# TurbochargerController_IR.net
KiCad netlist of a schematic drawn in EAGLE
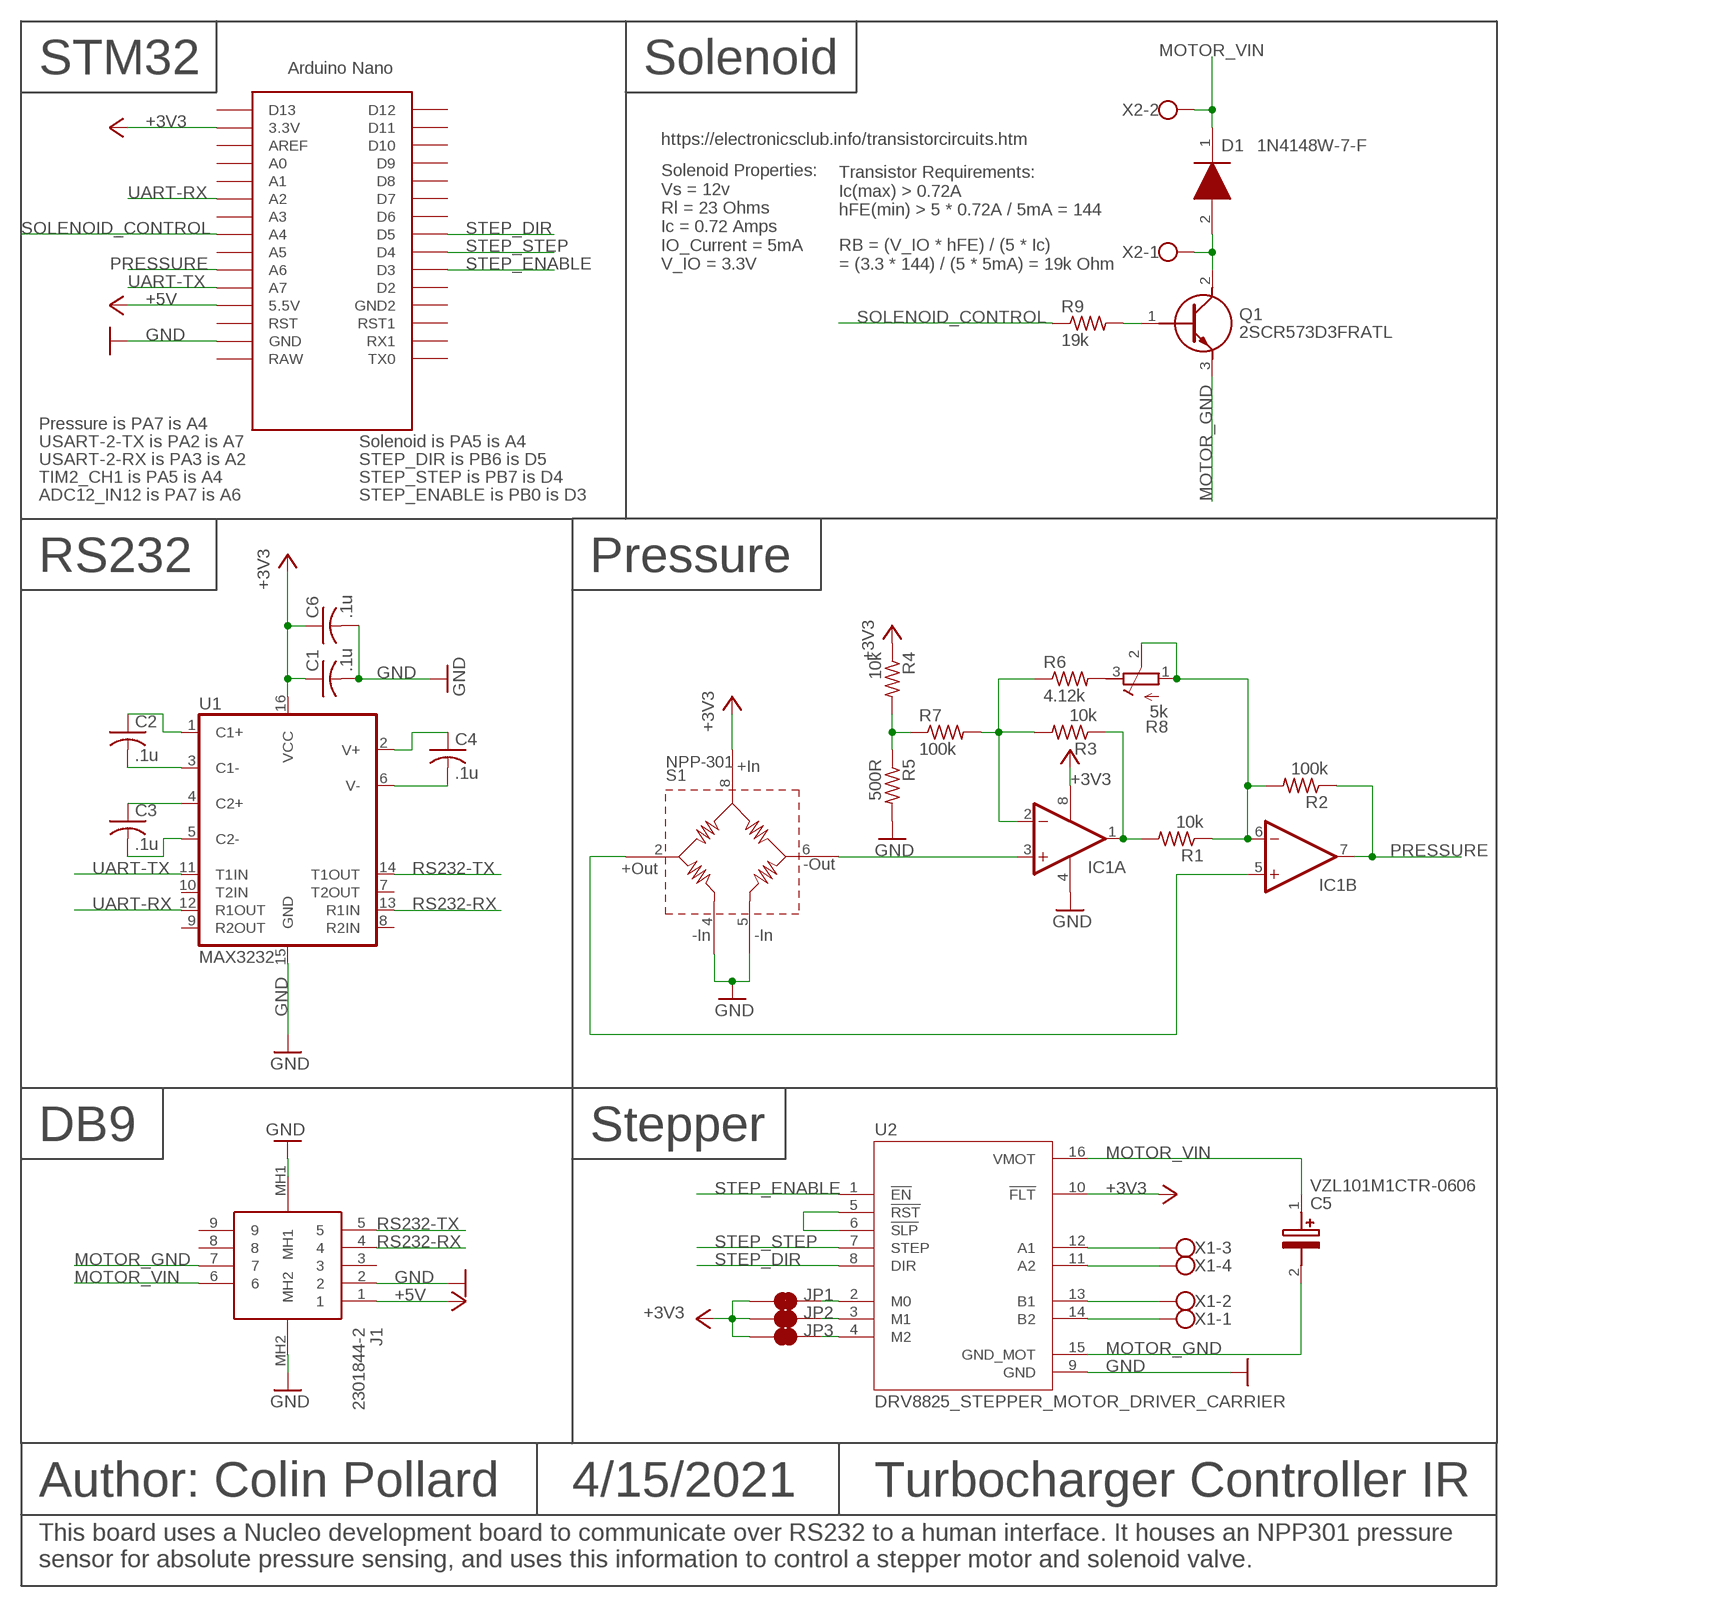
[diagram p0: schematic, sheet 1]

(export (version "E")
  (design (tool "Eeschema 10.0.6"))
  (components
    (comp (ref "C1")
      (value ".1u")
      (footprint "eagle-import:C1206")
      (libsource (lib "eagle-import") (part "C-USC1206"))
    )
    (comp (ref "C2")
      (value ".1u")
      (footprint "eagle-import:C1206")
      (libsource (lib "eagle-import") (part "C-USC1206"))
    )
    (comp (ref "C3")
      (value ".1u")
      (footprint "eagle-import:C1206")
      (libsource (lib "eagle-import") (part "C-USC1206"))
    )
    (comp (ref "C4")
      (value ".1u")
      (footprint "eagle-import:C1206")
      (libsource (lib "eagle-import") (part "C-USC1206"))
    )
    (comp (ref "C5")
      (value "VZL101M1CTR-0606")
      (footprint "eagle-import:CAPAE660X610N")
      (fields (field (name "MOUSER_PART_NUMBER") "140-VZL101M1CTR-0606"))
      (libsource (lib "eagle-import") (part "VZL101M1CTR-0606"))
    )
    (comp (ref "C6")
      (value ".1u")
      (footprint "eagle-import:C1206")
      (libsource (lib "eagle-import") (part "C-USC1206"))
    )
    (comp (ref "D1")
      (value "1N4148W-7-F")
      (footprint "eagle-import:SOD3716X145N")
      (fields (field (name "MOUSER_PART_NUMBER") "621-1N4148W-F"))
      (libsource (lib "eagle-import") (part "1N4148W-7-F"))
    )
    (comp (ref "IC1")
      (value "TL072D")
      (footprint "eagle-import:SO08")
      (libsource (lib "eagle-import") (part "TL072D"))
    )
    (comp (ref "J1")
      (value "2301844-2")
      (footprint "eagle-import:23018442")
      (fields (field (name "MOUSER_PART_NUMBER") "571-2301844-2"))
      (libsource (lib "eagle-import") (part "2301844-2"))
    )
    (comp (ref "JP1")
      (value "JUMPER-SMT_2_NC_TRACE_SILK")
      (footprint "eagle-import:SMT-JUMPER_2_NC_TRACE_SILK")
      (libsource (lib "eagle-import") (part "JUMPER-SMT_2_NC_TRACE_SILK"))
    )
    (comp (ref "JP2")
      (value "JUMPER-SMT_2_NC_TRACE_SILK")
      (footprint "eagle-import:SMT-JUMPER_2_NC_TRACE_SILK")
      (libsource (lib "eagle-import") (part "JUMPER-SMT_2_NC_TRACE_SILK"))
    )
    (comp (ref "JP3")
      (value "JUMPER-SMT_2_NC_TRACE_SILK")
      (footprint "eagle-import:SMT-JUMPER_2_NC_TRACE_SILK")
      (libsource (lib "eagle-import") (part "JUMPER-SMT_2_NC_TRACE_SILK"))
    )
    (comp (ref "Q1")
      (value "2SCR573D3FRATL")
      (footprint "eagle-import:2SCR573D3FRATL")
      (fields (field (name "MOUSER_PART_NUMBER") "755-2SCR573D3FRATL"))
      (libsource (lib "eagle-import") (part "2SCR573D3FRATL"))
    )
    (comp (ref "R1")
      (value "10k")
      (footprint "eagle-import:R1206")
      (libsource (lib "eagle-import") (part "R-US_R1206"))
    )
    (comp (ref "R2")
      (value "100k")
      (footprint "eagle-import:R1206")
      (libsource (lib "eagle-import") (part "R-US_R1206"))
    )
    (comp (ref "R3")
      (value "10k")
      (footprint "eagle-import:R1206")
      (libsource (lib "eagle-import") (part "R-US_R1206"))
    )
    (comp (ref "R4")
      (value "10k")
      (footprint "eagle-import:R1206")
      (libsource (lib "eagle-import") (part "R-US_R1206"))
    )
    (comp (ref "R5")
      (value "500R")
      (footprint "eagle-import:R1206")
      (libsource (lib "eagle-import") (part "R-US_R1206"))
    )
    (comp (ref "R6")
      (value "4.12k")
      (footprint "eagle-import:R1206")
      (libsource (lib "eagle-import") (part "R-US_R1206"))
    )
    (comp (ref "R7")
      (value "100k")
      (footprint "eagle-import:R1206")
      (libsource (lib "eagle-import") (part "R-US_R1206"))
    )
    (comp (ref "R8")
      (value "5k")
      (footprint "eagle-import:RTRIM3296W")
      (libsource (lib "eagle-import") (part "R-TRIMM3296W"))
    )
    (comp (ref "R9")
      (value "19k")
      (footprint "eagle-import:R1206")
      (libsource (lib "eagle-import") (part "R-US_R1206"))
    )
    (comp (ref "S1")
      (value "NPP-301")
      (footprint "eagle-import:SO08")
      (libsource (lib "eagle-import") (part "NPP-301"))
    )
    (comp (ref "U$1")
      (value "NANO")
      (footprint "eagle-import:NANO")
      (libsource (lib "eagle-import") (part "NANO"))
    )
    (comp (ref "U1")
      (value "MAX3232")
      (footprint "eagle-import:SO16")
      (libsource (lib "eagle-import") (part "MAX2323SOIC16"))
    )
    (comp (ref "U2")
      (value "DRV8825_STEPPER_MOTOR_DRIVER_CARRIER")
      (footprint "eagle-import:IC_DRV8825_STEPPER_MOTOR_DRIVER_CARRIER")
      (fields (field (name "MF") "Pololu") (field (name "MP") "DRV8825 STEPPER MOTOR DRIVER CARRIER"))
      (libsource (lib "eagle-import") (part "DRV8825_STEPPER_MOTOR_DRIVER_CARRIER"))
    )
    (comp (ref "X1")
      (value "W237-4")
      (footprint "eagle-import:W237-4")
      (libsource (lib "eagle-import") (part "W237-4"))
    )
    (comp (ref "X2")
      (value "W237-102")
      (footprint "eagle-import:W237-102")
      (fields (field (name "MPN") "237-102"))
      (libsource (lib "eagle-import") (part "W237-102"))
    )
  )
  (nets
    (net (code "1") (name "+3V3") (class "Default")
      (node (ref "C1") (pin "1") (pinfunction "1_1") (pintype "passive"))
      (node (ref "C6") (pin "1") (pinfunction "1_1") (pintype "passive"))
      (node (ref "IC1") (pin "8") (pinfunction "V+_8") (pintype "power_in"))
      (node (ref "JP1") (pin "1") (pinfunction "1_1") (pintype "passive"))
      (node (ref "JP2") (pin "1") (pinfunction "1_1") (pintype "passive"))
      (node (ref "JP3") (pin "1") (pinfunction "1_1") (pintype "passive"))
      (node (ref "R4") (pin "1") (pinfunction "1_1") (pintype "passive"))
      (node (ref "S1") (pin "8") (pinfunction "+IN_8") (pintype "input"))
      (node (ref "U$1") (pin "3.3V") (pinfunction "3.3V_3.3V") (pintype "bidirectional"))
      (node (ref "U1") (pin "16") (pinfunction "VCC_16") (pintype "bidirectional"))
      (node (ref "U2") (pin "10") (pinfunction "~{FLT}_10") (pintype "output"))
    )
    (net (code "2") (name "+5V") (class "Default")
      (node (ref "J1") (pin "1") (pinfunction "1_1") (pintype "bidirectional"))
      (node (ref "U$1") (pin "5V") (pinfunction "5.5V_5V") (pintype "bidirectional"))
    )
    (net (code "3") (name "/MOTOR_GND") (class "Default")
      (node (ref "C5") (pin "2") (pinfunction "-_2") (pintype "bidirectional"))
      (node (ref "J1") (pin "7") (pinfunction "7_7") (pintype "bidirectional"))
      (node (ref "Q1") (pin "3") (pinfunction "E_3") (pintype "bidirectional"))
      (node (ref "U2") (pin "15") (pinfunction "GND_MOT_15") (pintype "power_in"))
    )
    (net (code "4") (name "/MOTOR_VIN") (class "Default")
      (node (ref "C5") (pin "1") (pinfunction "+_1") (pintype "bidirectional"))
      (node (ref "D1") (pin "1") (pinfunction "K_1") (pintype "bidirectional"))
      (node (ref "J1") (pin "6") (pinfunction "6_6") (pintype "bidirectional"))
      (node (ref "U2") (pin "16") (pinfunction "VMOT_16") (pintype "power_in"))
      (node (ref "X2") (pin "2") (pinfunction "KL_2") (pintype "passive"))
    )
    (net (code "5") (name "/PRESSURE") (class "Default")
      (node (ref "IC1") (pin "7") (pinfunction "OUT_7") (pintype "output"))
      (node (ref "R2") (pin "1") (pinfunction "1_1") (pintype "passive"))
      (node (ref "U$1") (pin "A6") (pinfunction "A6_A6") (pintype "bidirectional"))
    )
    (net (code "6") (name "/RS232-RX") (class "Default")
      (node (ref "J1") (pin "4") (pinfunction "4_4") (pintype "bidirectional"))
      (node (ref "U1") (pin "13") (pinfunction "R1IN_13") (pintype "input"))
    )
    (net (code "7") (name "/RS232-TX") (class "Default")
      (node (ref "J1") (pin "5") (pinfunction "5_5") (pintype "bidirectional"))
      (node (ref "U1") (pin "14") (pinfunction "T1OUT_14") (pintype "output"))
    )
    (net (code "8") (name "/SOLENOID_CONTROL") (class "Default")
      (node (ref "R9") (pin "1") (pinfunction "1_1") (pintype "passive"))
      (node (ref "U$1") (pin "A4") (pinfunction "A4_A4") (pintype "bidirectional"))
    )
    (net (code "9") (name "/STEP_DIR") (class "Default")
      (node (ref "U$1") (pin "D5") (pinfunction "D5_D5") (pintype "bidirectional"))
      (node (ref "U2") (pin "8") (pinfunction "DIR_8") (pintype "input"))
    )
    (net (code "10") (name "/STEP_ENABLE") (class "Default")
      (node (ref "U$1") (pin "D3") (pinfunction "D3_D3") (pintype "bidirectional"))
      (node (ref "U2") (pin "1") (pinfunction "~{EN}_1") (pintype "input"))
    )
    (net (code "11") (name "/STEP_STEP") (class "Default")
      (node (ref "U$1") (pin "D4") (pinfunction "D4_D4") (pintype "bidirectional"))
      (node (ref "U2") (pin "7") (pinfunction "STEP_7") (pintype "input"))
    )
    (net (code "12") (name "/UART-RX") (class "Default")
      (node (ref "U$1") (pin "A2") (pinfunction "A2_A2") (pintype "bidirectional"))
      (node (ref "U1") (pin "12") (pinfunction "R1OUT_12") (pintype "output"))
    )
    (net (code "13") (name "/UART-TX") (class "Default")
      (node (ref "U$1") (pin "A7") (pinfunction "A7_A7") (pintype "bidirectional"))
      (node (ref "U1") (pin "11") (pinfunction "T1IN_11") (pintype "input"))
    )
    (net (code "14") (name "GND") (class "Default")
      (node (ref "C1") (pin "2") (pinfunction "2_2") (pintype "passive"))
      (node (ref "C6") (pin "2") (pinfunction "2_2") (pintype "passive"))
      (node (ref "IC1") (pin "4") (pinfunction "V-_4") (pintype "power_in"))
      (node (ref "J1") (pin "2") (pinfunction "2_2") (pintype "bidirectional"))
      (node (ref "J1") (pin "MH1") (pinfunction "MH1_MH1") (pintype "bidirectional"))
      (node (ref "J1") (pin "MH2") (pinfunction "MH2_MH2") (pintype "bidirectional"))
      (node (ref "R5") (pin "2") (pinfunction "2_2") (pintype "passive"))
      (node (ref "S1") (pin "4") (pinfunction "-IN_1_4") (pintype "input"))
      (node (ref "S1") (pin "5") (pinfunction "-IN_2_5") (pintype "input"))
      (node (ref "U$1") (pin "GND") (pinfunction "GND_GND") (pintype "bidirectional"))
      (node (ref "U1") (pin "15") (pinfunction "GND_15") (pintype "bidirectional"))
      (node (ref "U2") (pin "9") (pinfunction "GND_9") (pintype "power_in"))
    )
    (net (code "15") (name "Net-(D1-A)") (class "Default")
      (node (ref "D1") (pin "2") (pinfunction "A_2") (pintype "bidirectional"))
      (node (ref "Q1") (pin "2") (pinfunction "C_2") (pintype "bidirectional"))
      (node (ref "X2") (pin "1") (pinfunction "KL_1") (pintype "passive"))
    )
    (net (code "16") (name "Net-(IC1A-+IN)") (class "Default")
      (node (ref "IC1") (pin "3") (pinfunction "+IN_3") (pintype "input"))
      (node (ref "S1") (pin "6") (pinfunction "-OUT_6") (pintype "output"))
    )
    (net (code "17") (name "Net-(IC1A--IN)") (class "Default")
      (node (ref "IC1") (pin "2") (pinfunction "-IN_2") (pintype "input"))
      (node (ref "R3") (pin "2") (pinfunction "2_2") (pintype "passive"))
      (node (ref "R6") (pin "1") (pinfunction "1_1") (pintype "passive"))
      (node (ref "R7") (pin "2") (pinfunction "2_2") (pintype "passive"))
    )
    (net (code "18") (name "Net-(IC1A-OUT)") (class "Default")
      (node (ref "IC1") (pin "1") (pinfunction "OUT_1") (pintype "output"))
      (node (ref "R1") (pin "2") (pinfunction "2_2") (pintype "passive"))
      (node (ref "R3") (pin "1") (pinfunction "1_1") (pintype "passive"))
    )
    (net (code "19") (name "Net-(IC1B-+IN)") (class "Default")
      (node (ref "IC1") (pin "5") (pinfunction "+IN_5") (pintype "input"))
      (node (ref "S1") (pin "2") (pinfunction "+OUT_2") (pintype "output"))
    )
    (net (code "20") (name "Net-(IC1B--IN)") (class "Default")
      (node (ref "IC1") (pin "6") (pinfunction "-IN_6") (pintype "input"))
      (node (ref "R1") (pin "1") (pinfunction "1_1") (pintype "passive"))
      (node (ref "R2") (pin "2") (pinfunction "2_2") (pintype "passive"))
      (node (ref "R8") (pin "1") (pinfunction "A_1") (pintype "passive"))
      (node (ref "R8") (pin "2") (pinfunction "S_2") (pintype "passive"))
    )
    (net (code "21") (name "Net-(Q1-B)") (class "Default")
      (node (ref "Q1") (pin "1") (pinfunction "B_1") (pintype "bidirectional"))
      (node (ref "R9") (pin "2") (pinfunction "2_2") (pintype "passive"))
    )
    (net (code "22") (name "Net-(R4-Pad2)") (class "Default")
      (node (ref "R4") (pin "2") (pinfunction "2_2") (pintype "passive"))
      (node (ref "R5") (pin "1") (pinfunction "1_1") (pintype "passive"))
      (node (ref "R7") (pin "1") (pinfunction "1_1") (pintype "passive"))
    )
    (net (code "23") (name "Net-(R8-E)") (class "Default")
      (node (ref "R6") (pin "2") (pinfunction "2_2") (pintype "passive"))
      (node (ref "R8") (pin "3") (pinfunction "E_3") (pintype "passive"))
    )
    (net (code "24") (name "Net-(U1-C1+)") (class "Default")
      (node (ref "C2") (pin "1") (pinfunction "1_1") (pintype "passive"))
      (node (ref "U1") (pin "1") (pinfunction "C1+_1") (pintype "bidirectional"))
    )
    (net (code "25") (name "Net-(U1-C1-)") (class "Default")
      (node (ref "C2") (pin "2") (pinfunction "2_2") (pintype "passive"))
      (node (ref "U1") (pin "3") (pinfunction "C1-_3") (pintype "bidirectional"))
    )
    (net (code "26") (name "Net-(U1-C2+)") (class "Default")
      (node (ref "C3") (pin "1") (pinfunction "1_1") (pintype "passive"))
      (node (ref "U1") (pin "4") (pinfunction "C2+_4") (pintype "bidirectional"))
    )
    (net (code "27") (name "Net-(U1-C2-)") (class "Default")
      (node (ref "C3") (pin "2") (pinfunction "2_2") (pintype "passive"))
      (node (ref "U1") (pin "5") (pinfunction "C2-_5") (pintype "bidirectional"))
    )
    (net (code "28") (name "Net-(U1-V+)") (class "Default")
      (node (ref "C4") (pin "1") (pinfunction "1_1") (pintype "passive"))
      (node (ref "U1") (pin "2") (pinfunction "V+_2") (pintype "bidirectional"))
    )
    (net (code "29") (name "Net-(U1-V-)") (class "Default")
      (node (ref "C4") (pin "2") (pinfunction "2_2") (pintype "passive"))
      (node (ref "U1") (pin "6") (pinfunction "V-_6") (pintype "bidirectional"))
    )
    (net (code "30") (name "Net-(U2-A1)") (class "Default")
      (node (ref "U2") (pin "12") (pinfunction "A1_12") (pintype "output"))
      (node (ref "X1") (pin "3") (pinfunction "KL_3") (pintype "passive"))
    )
    (net (code "31") (name "Net-(U2-A2)") (class "Default")
      (node (ref "U2") (pin "11") (pinfunction "A2_11") (pintype "output"))
      (node (ref "X1") (pin "4") (pinfunction "KL_4") (pintype "passive"))
    )
    (net (code "32") (name "Net-(U2-B1)") (class "Default")
      (node (ref "U2") (pin "13") (pinfunction "B1_13") (pintype "output"))
      (node (ref "X1") (pin "2") (pinfunction "KL_2") (pintype "passive"))
    )
    (net (code "33") (name "Net-(U2-B2)") (class "Default")
      (node (ref "U2") (pin "14") (pinfunction "B2_14") (pintype "output"))
      (node (ref "X1") (pin "1") (pinfunction "KL_1") (pintype "passive"))
    )
    (net (code "34") (name "Net-(U2-M0)") (class "Default")
      (node (ref "JP1") (pin "2") (pinfunction "2_2") (pintype "passive"))
      (node (ref "U2") (pin "2") (pinfunction "M0_2") (pintype "input"))
    )
    (net (code "35") (name "Net-(U2-M1)") (class "Default")
      (node (ref "JP2") (pin "2") (pinfunction "2_2") (pintype "passive"))
      (node (ref "U2") (pin "3") (pinfunction "M1_3") (pintype "input"))
    )
    (net (code "36") (name "Net-(U2-M2)") (class "Default")
      (node (ref "JP3") (pin "2") (pinfunction "2_2") (pintype "passive"))
      (node (ref "U2") (pin "4") (pinfunction "M2_4") (pintype "input"))
    )
    (net (code "37") (name "Net-(U2-~{RST})") (class "Default")
      (node (ref "U2") (pin "5") (pinfunction "~{RST}_5") (pintype "input"))
      (node (ref "U2") (pin "6") (pinfunction "~{SLP}_6") (pintype "input"))
    )
    (net (code "38") (name "unconnected-(J1-Pad3)") (class "Default")
      (node (ref "J1") (pin "3") (pinfunction "3_3") (pintype "bidirectional"))
    )
    (net (code "39") (name "unconnected-(J1-Pad8)") (class "Default")
      (node (ref "J1") (pin "8") (pinfunction "8_8") (pintype "bidirectional"))
    )
    (net (code "40") (name "unconnected-(J1-Pad9)") (class "Default")
      (node (ref "J1") (pin "9") (pinfunction "9_9") (pintype "bidirectional"))
    )
    (net (code "41") (name "unconnected-(U$1-GND2-PadGND1)") (class "Default")
      (node (ref "U$1") (pin "GND1") (pinfunction "GND2_GND1") (pintype "bidirectional"))
    )
    (net (code "42") (name "unconnected-(U$1-PadA0)") (class "Default")
      (node (ref "U$1") (pin "A0") (pinfunction "A0_A0") (pintype "bidirectional"))
    )
    (net (code "43") (name "unconnected-(U$1-PadA1)") (class "Default")
      (node (ref "U$1") (pin "A1") (pinfunction "A1_A1") (pintype "bidirectional"))
    )
    (net (code "44") (name "unconnected-(U$1-PadA3)") (class "Default")
      (node (ref "U$1") (pin "A3") (pinfunction "A3_A3") (pintype "bidirectional"))
    )
    (net (code "45") (name "unconnected-(U$1-PadA5)") (class "Default")
      (node (ref "U$1") (pin "A5") (pinfunction "A5_A5") (pintype "bidirectional"))
    )
    (net (code "46") (name "unconnected-(U$1-PadAREF)") (class "Default")
      (node (ref "U$1") (pin "AREF") (pinfunction "AREF_AREF") (pintype "bidirectional"))
    )
    (net (code "47") (name "unconnected-(U$1-PadD2)") (class "Default")
      (node (ref "U$1") (pin "D2") (pinfunction "D2_D2") (pintype "bidirectional"))
    )
    (net (code "48") (name "unconnected-(U$1-PadD6)") (class "Default")
      (node (ref "U$1") (pin "D6") (pinfunction "D6_D6") (pintype "bidirectional"))
    )
    (net (code "49") (name "unconnected-(U$1-PadD7)") (class "Default")
      (node (ref "U$1") (pin "D7") (pinfunction "D7_D7") (pintype "bidirectional"))
    )
    (net (code "50") (name "unconnected-(U$1-PadD8)") (class "Default")
      (node (ref "U$1") (pin "D8") (pinfunction "D8_D8") (pintype "bidirectional"))
    )
    (net (code "51") (name "unconnected-(U$1-PadD9)") (class "Default")
      (node (ref "U$1") (pin "D9") (pinfunction "D9_D9") (pintype "bidirectional"))
    )
    (net (code "52") (name "unconnected-(U$1-PadD10)") (class "Default")
      (node (ref "U$1") (pin "D10") (pinfunction "D10_D10") (pintype "bidirectional"))
    )
    (net (code "53") (name "unconnected-(U$1-PadD11)") (class "Default")
      (node (ref "U$1") (pin "D11") (pinfunction "D11_D11") (pintype "bidirectional"))
    )
    (net (code "54") (name "unconnected-(U$1-PadD12)") (class "Default")
      (node (ref "U$1") (pin "D12") (pinfunction "D12_D12") (pintype "bidirectional"))
    )
    (net (code "55") (name "unconnected-(U$1-PadD13)") (class "Default")
      (node (ref "U$1") (pin "D13") (pinfunction "D13_D13") (pintype "bidirectional"))
    )
    (net (code "56") (name "unconnected-(U$1-PadICSP1)") (class "Default")
      (node (ref "U$1") (pin "ICSP1") (pinfunction "ICSP1_ICSP1") (pintype "bidirectional"))
    )
    (net (code "57") (name "unconnected-(U$1-PadICSP2)") (class "Default")
      (node (ref "U$1") (pin "ICSP2") (pinfunction "ICSP2_ICSP2") (pintype "bidirectional"))
    )
    (net (code "58") (name "unconnected-(U$1-PadICSP3)") (class "Default")
      (node (ref "U$1") (pin "ICSP3") (pinfunction "ICSP3_ICSP3") (pintype "bidirectional"))
    )
    (net (code "59") (name "unconnected-(U$1-PadICSP4)") (class "Default")
      (node (ref "U$1") (pin "ICSP4") (pinfunction "ICSP4_ICSP4") (pintype "bidirectional"))
    )
    (net (code "60") (name "unconnected-(U$1-PadICSP5)") (class "Default")
      (node (ref "U$1") (pin "ICSP5") (pinfunction "ICSP5_ICSP5") (pintype "bidirectional"))
    )
    (net (code "61") (name "unconnected-(U$1-PadICSP6)") (class "Default")
      (node (ref "U$1") (pin "ICSP6") (pinfunction "ICSP6_ICSP6") (pintype "bidirectional"))
    )
    (net (code "62") (name "unconnected-(U$1-PadRAW)") (class "Default")
      (node (ref "U$1") (pin "RAW") (pinfunction "RAW_RAW") (pintype "bidirectional"))
    )
    (net (code "63") (name "unconnected-(U$1-PadRST)") (class "Default")
      (node (ref "U$1") (pin "RST") (pinfunction "RST_RST") (pintype "bidirectional"))
    )
    (net (code "64") (name "unconnected-(U$1-PadRST1)") (class "Default")
      (node (ref "U$1") (pin "RST1") (pinfunction "RST1_RST1") (pintype "bidirectional"))
    )
    (net (code "65") (name "unconnected-(U$1-PadRX1)") (class "Default")
      (node (ref "U$1") (pin "RX1") (pinfunction "RX1_RX1") (pintype "bidirectional"))
    )
    (net (code "66") (name "unconnected-(U$1-PadTX0)") (class "Default")
      (node (ref "U$1") (pin "TX0") (pinfunction "TX0_TX0") (pintype "bidirectional"))
    )
    (net (code "67") (name "unconnected-(U1-R2IN-Pad8)") (class "Default")
      (node (ref "U1") (pin "8") (pinfunction "R2IN_8") (pintype "input"))
    )
    (net (code "68") (name "unconnected-(U1-R2OUT-Pad9)") (class "Default")
      (node (ref "U1") (pin "9") (pinfunction "R2OUT_9") (pintype "output"))
    )
    (net (code "69") (name "unconnected-(U1-T2IN-Pad10)") (class "Default")
      (node (ref "U1") (pin "10") (pinfunction "T2IN_10") (pintype "input"))
    )
    (net (code "70") (name "unconnected-(U1-T2OUT-Pad7)") (class "Default")
      (node (ref "U1") (pin "7") (pinfunction "T2OUT_7") (pintype "output"))
    )
  )
)
